# ws1_try.net
KiCad netlist of a schematic drawn in EAGLE
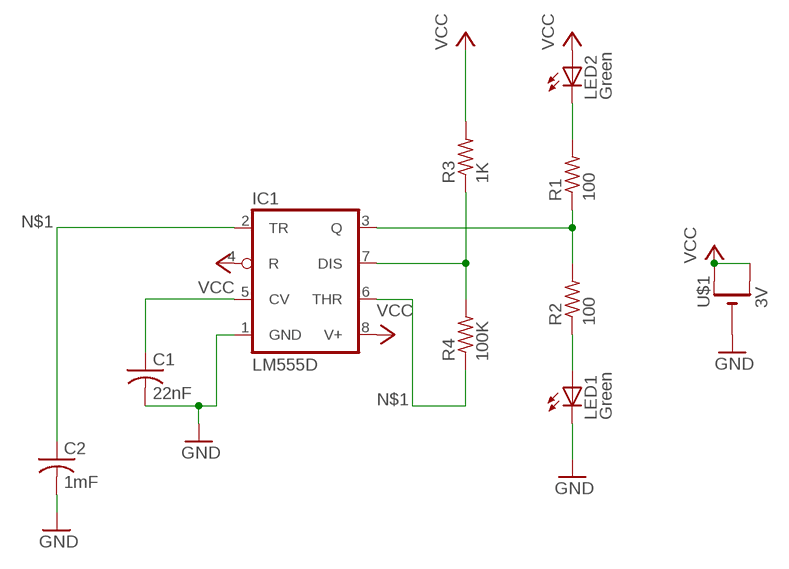
[diagram p0: schematic, sheet 1]

(export (version "E")
  (design (tool "Eeschema 10.0.6"))
  (components
    (comp (ref "C1")
      (value "22nF")
      (footprint "eagle-import:C0805")
      (libsource (lib "eagle-import") (part "C-USC0805"))
    )
    (comp (ref "C2")
      (value "1mF")
      (footprint "eagle-import:C0805")
      (libsource (lib "eagle-import") (part "C-USC0805"))
    )
    (comp (ref "IC1")
      (value "LM555D")
      (footprint "eagle-import:SO08")
      (libsource (lib "eagle-import") (part "555DLM"))
    )
    (comp (ref "LED1")
      (value "Green")
      (footprint "eagle-import:CHIP-LED0805")
      (libsource (lib "eagle-import") (part "LEDCHIP-LED0805"))
    )
    (comp (ref "LED2")
      (value "Green")
      (footprint "eagle-import:CHIP-LED0805")
      (libsource (lib "eagle-import") (part "LEDCHIP-LED0805"))
    )
    (comp (ref "R1")
      (value "100")
      (footprint "eagle-import:R0805")
      (libsource (lib "eagle-import") (part "R-US_R0805"))
    )
    (comp (ref "R2")
      (value "100")
      (footprint "eagle-import:R0805")
      (libsource (lib "eagle-import") (part "R-US_R0805"))
    )
    (comp (ref "R3")
      (value "1K")
      (footprint "eagle-import:R0805")
      (libsource (lib "eagle-import") (part "R-US_R0805"))
    )
    (comp (ref "R4")
      (value "100K")
      (footprint "eagle-import:R0805")
      (libsource (lib "eagle-import") (part "R-US_R0805"))
    )
    (comp (ref "U$1")
      (value "3V")
      (footprint "eagle-import:CR1220-SMD")
      (libsource (lib "eagle-import") (part "CR1220SMT"))
    )
  )
  (nets
    (net (code "1") (name "/N$1") (class "Default")
      (node (ref "C2") (pin "1") (pinfunction "1_1") (pintype "passive"))
      (node (ref "IC1") (pin "2") (pinfunction "TR_2") (pintype "input"))
      (node (ref "IC1") (pin "6") (pinfunction "THR_6") (pintype "input"))
      (node (ref "R4") (pin "1") (pinfunction "1_1") (pintype "passive"))
    )
    (net (code "2") (name "GND") (class "Default")
      (node (ref "C1") (pin "2") (pinfunction "2_2") (pintype "passive"))
      (node (ref "C2") (pin "2") (pinfunction "2_2") (pintype "passive"))
      (node (ref "IC1") (pin "1") (pinfunction "GND_1") (pintype "power_in"))
      (node (ref "LED1") (pin "C") (pinfunction "C_C") (pintype "passive"))
      (node (ref "U$1") (pin "-") (pinfunction "-_-") (pintype "passive"))
    )
    (net (code "3") (name "Net-(IC1-CV)") (class "Default")
      (node (ref "C1") (pin "1") (pinfunction "1_1") (pintype "passive"))
      (node (ref "IC1") (pin "5") (pinfunction "CV_5") (pintype "input"))
    )
    (net (code "4") (name "Net-(IC1-DIS)") (class "Default")
      (node (ref "IC1") (pin "7") (pinfunction "DIS_7") (pintype "input"))
      (node (ref "R3") (pin "1") (pinfunction "1_1") (pintype "passive"))
      (node (ref "R4") (pin "2") (pinfunction "2_2") (pintype "passive"))
    )
    (net (code "5") (name "Net-(IC1-Q)") (class "Default")
      (node (ref "IC1") (pin "3") (pinfunction "Q_3") (pintype "output"))
      (node (ref "R1") (pin "1") (pinfunction "1_1") (pintype "passive"))
      (node (ref "R2") (pin "2") (pinfunction "2_2") (pintype "passive"))
    )
    (net (code "6") (name "Net-(LED1-PadA)") (class "Default")
      (node (ref "LED1") (pin "A") (pinfunction "A_A") (pintype "passive"))
      (node (ref "R2") (pin "1") (pinfunction "1_1") (pintype "passive"))
    )
    (net (code "7") (name "Net-(LED2-PadC)") (class "Default")
      (node (ref "LED2") (pin "C") (pinfunction "C_C") (pintype "passive"))
      (node (ref "R1") (pin "2") (pinfunction "2_2") (pintype "passive"))
    )
    (net (code "8") (name "VCC") (class "Default")
      (node (ref "IC1") (pin "4") (pinfunction "R_4") (pintype "input"))
      (node (ref "IC1") (pin "8") (pinfunction "V+_8") (pintype "power_in"))
      (node (ref "LED2") (pin "A") (pinfunction "A_A") (pintype "passive"))
      (node (ref "R3") (pin "2") (pinfunction "2_2") (pintype "passive"))
      (node (ref "U$1") (pin "+$1") (pinfunction "+_+$1") (pintype "passive"))
      (node (ref "U$1") (pin "+$2") (pinfunction "+1_+$2") (pintype "passive"))
    )
  )
)
